# PW_TPS6213x_TestDemo.net
KiCad netlist of a schematic drawn in Altium Designer
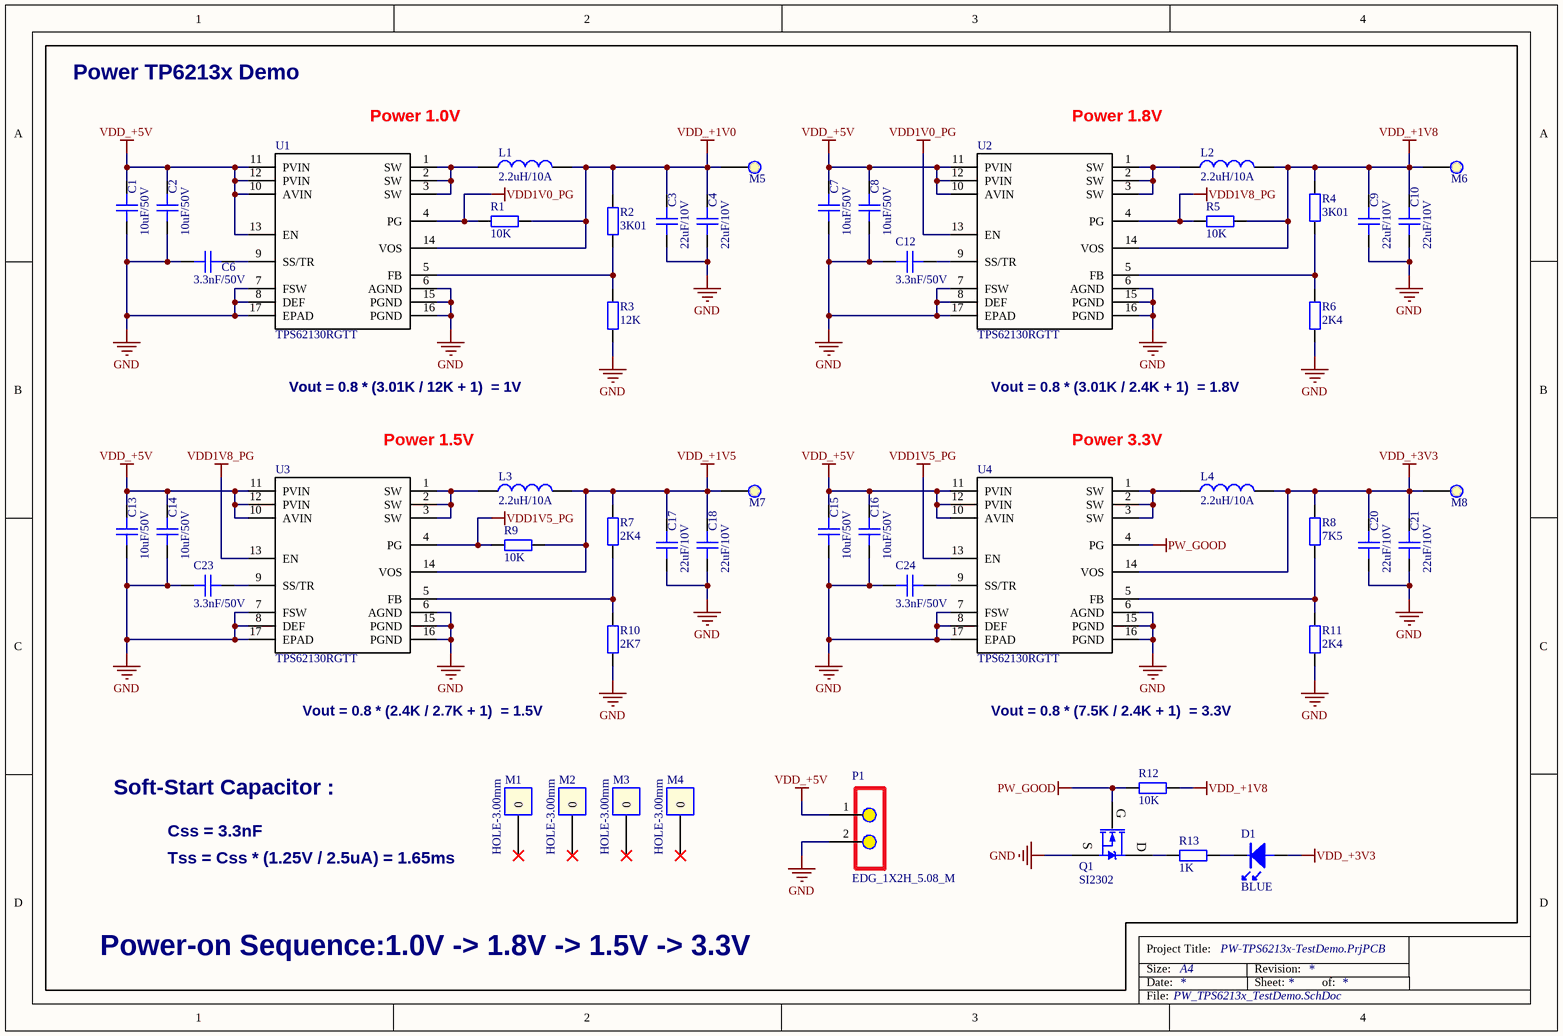
[diagram p0: PW_TPS6213x_TestDemo.SchDoc]

(export (version "E")
  (design (tool "Eeschema 10.0.6"))
  (components
    (comp (ref "C1")
      (value "10uF/50V")
      (footprint "C1206")
      (fields (field (name "Comment") "C_B2_10uF_50V_C1206_20%"))
      (libsource (lib "Fangling DXP Lib") (part "C_B2_10uF_50V_C1206_20%"))
    )
    (comp (ref "C2")
      (value "10uF/50V")
      (footprint "C1206")
      (fields (field (name "Comment") "C_B2_10uF_50V_C1206_20%"))
      (libsource (lib "Fangling DXP Lib") (part "C_B2_10uF_50V_C1206_20%"))
    )
    (comp (ref "C3")
      (value "22uF/10V")
      (footprint "C0805")
      (description "X5R")
      (fields (field (name "Comment") "C_B2_22uF_10V_C0805_20%"))
      (libsource (lib "Fangling DXP Lib") (part "C_B2_22uF_10V_C0805_20%"))
    )
    (comp (ref "C4")
      (value "22uF/10V")
      (footprint "C0805")
      (description "X5R")
      (fields (field (name "Comment") "C_B2_22uF_10V_C0805_20%"))
      (libsource (lib "Fangling DXP Lib") (part "C_B2_22uF_10V_C0805_20%"))
    )
    (comp (ref "C6")
      (value "3.3nF/50V")
      (footprint "C0603")
      (fields (field (name "Comment") "C_B2_3.3nF_50V_C0603_10%"))
      (libsource (lib "UserLib") (part "C_B2_3.3nF_50V_C0603_10%"))
    )
    (comp (ref "C7")
      (value "10uF/50V")
      (footprint "C1206")
      (fields (field (name "Comment") "C_B2_10uF_50V_C1206_20%"))
      (libsource (lib "Fangling DXP Lib") (part "C_B2_10uF_50V_C1206_20%"))
    )
    (comp (ref "C8")
      (value "10uF/50V")
      (footprint "C1206")
      (fields (field (name "Comment") "C_B2_10uF_50V_C1206_20%"))
      (libsource (lib "Fangling DXP Lib") (part "C_B2_10uF_50V_C1206_20%"))
    )
    (comp (ref "C9")
      (value "22uF/10V")
      (footprint "C0805")
      (description "X5R")
      (fields (field (name "Comment") "C_B2_22uF_10V_C0805_20%"))
      (libsource (lib "Fangling DXP Lib") (part "C_B2_22uF_10V_C0805_20%"))
    )
    (comp (ref "C10")
      (value "22uF/10V")
      (footprint "C0805")
      (description "X5R")
      (fields (field (name "Comment") "C_B2_22uF_10V_C0805_20%"))
      (libsource (lib "Fangling DXP Lib") (part "C_B2_22uF_10V_C0805_20%"))
    )
    (comp (ref "C12")
      (value "3.3nF/50V")
      (footprint "C0603")
      (fields (field (name "Comment") "C_B2_3.3nF_50V_C0603_10%"))
      (libsource (lib "UserLib") (part "C_B2_3.3nF_50V_C0603_10%"))
    )
    (comp (ref "C13")
      (value "10uF/50V")
      (footprint "C1206")
      (fields (field (name "Comment") "C_B2_10uF_50V_C1206_20%"))
      (libsource (lib "Fangling DXP Lib") (part "C_B2_10uF_50V_C1206_20%"))
    )
    (comp (ref "C14")
      (value "10uF/50V")
      (footprint "C1206")
      (fields (field (name "Comment") "C_B2_10uF_50V_C1206_20%"))
      (libsource (lib "Fangling DXP Lib") (part "C_B2_10uF_50V_C1206_20%"))
    )
    (comp (ref "C15")
      (value "10uF/50V")
      (footprint "C1206")
      (fields (field (name "Comment") "C_B2_10uF_50V_C1206_20%"))
      (libsource (lib "Fangling DXP Lib") (part "C_B2_10uF_50V_C1206_20%"))
    )
    (comp (ref "C16")
      (value "10uF/50V")
      (footprint "C1206")
      (fields (field (name "Comment") "C_B2_10uF_50V_C1206_20%"))
      (libsource (lib "Fangling DXP Lib") (part "C_B2_10uF_50V_C1206_20%"))
    )
    (comp (ref "C17")
      (value "22uF/10V")
      (footprint "C0805")
      (description "X5R")
      (fields (field (name "Comment") "C_B2_22uF_10V_C0805_20%"))
      (libsource (lib "Fangling DXP Lib") (part "C_B2_22uF_10V_C0805_20%"))
    )
    (comp (ref "C18")
      (value "22uF/10V")
      (footprint "C0805")
      (description "X5R")
      (fields (field (name "Comment") "C_B2_22uF_10V_C0805_20%"))
      (libsource (lib "Fangling DXP Lib") (part "C_B2_22uF_10V_C0805_20%"))
    )
    (comp (ref "C20")
      (value "22uF/10V")
      (footprint "C0805")
      (description "X5R")
      (fields (field (name "Comment") "C_B2_22uF_10V_C0805_20%"))
      (libsource (lib "Fangling DXP Lib") (part "C_B2_22uF_10V_C0805_20%"))
    )
    (comp (ref "C21")
      (value "22uF/10V")
      (footprint "C0805")
      (description "X5R")
      (fields (field (name "Comment") "C_B2_22uF_10V_C0805_20%"))
      (libsource (lib "Fangling DXP Lib") (part "C_B2_22uF_10V_C0805_20%"))
    )
    (comp (ref "C23")
      (value "3.3nF/50V")
      (footprint "C0603")
      (fields (field (name "Comment") "C_B2_3.3nF_50V_C0603_10%"))
      (libsource (lib "UserLib") (part "C_B2_3.3nF_50V_C0603_10%"))
    )
    (comp (ref "C24")
      (value "3.3nF/50V")
      (footprint "C0603")
      (fields (field (name "Comment") "C_B2_3.3nF_50V_C0603_10%"))
      (libsource (lib "UserLib") (part "C_B2_3.3nF_50V_C0603_10%"))
    )
    (comp (ref "D1")
      (value "BLUE")
      (footprint "LED0805")
      (fields (field (name "Comment") "D_D2_LED-BLUE_LED0805"))
      (libsource (lib "Fangling DXP Lib") (part "D_D2_LED-BLUE_LED0805"))
    )
    (comp (ref "L1")
      (value "2.2uH/10A")
      (footprint "L_MWSA0603S")
      (fields (field (name "Comment") "L_C2_2.2uH_10A_MWSA0603S_20%_(MWSA0603S-2R2MT)"))
      (libsource (lib "UserLib") (part "L_C2_2.2uH_10A_MWSA0603S_20%_(MWSA0603S-2R2MT)"))
    )
    (comp (ref "L2")
      (value "2.2uH/10A")
      (footprint "L_MWSA0603S")
      (fields (field (name "Comment") "L_C2_2.2uH_10A_MWSA0603S_20%_(MWSA0603S-2R2MT)"))
      (libsource (lib "UserLib") (part "L_C2_2.2uH_10A_MWSA0603S_20%_(MWSA0603S-2R2MT)"))
    )
    (comp (ref "L3")
      (value "2.2uH/10A")
      (footprint "L_MWSA0603S")
      (fields (field (name "Comment") "L_C2_2.2uH_10A_MWSA0603S_20%_(MWSA0603S-2R2MT)"))
      (libsource (lib "UserLib") (part "L_C2_2.2uH_10A_MWSA0603S_20%_(MWSA0603S-2R2MT)"))
    )
    (comp (ref "L4")
      (value "2.2uH/10A")
      (footprint "L_MWSA0603S")
      (fields (field (name "Comment") "L_C2_2.2uH_10A_MWSA0603S_20%_(MWSA0603S-2R2MT)"))
      (libsource (lib "UserLib") (part "L_C2_2.2uH_10A_MWSA0603S_20%_(MWSA0603S-2R2MT)"))
    )
    (comp (ref "M1")
      (value "HOLE-3.00mm")
      (footprint "M3 3.5x6mm")
      (description "M_HOLE-3.00mm")
      (libsource (lib "Fangling DXP Lib") (part "M_HOLE-3.00mm"))
    )
    (comp (ref "M2")
      (value "HOLE-3.00mm")
      (footprint "M3 3.5x6mm")
      (description "M_HOLE-3.00mm")
      (libsource (lib "Fangling DXP Lib") (part "M_HOLE-3.00mm"))
    )
    (comp (ref "M3")
      (value "HOLE-3.00mm")
      (footprint "M3 3.5x6mm")
      (description "M_HOLE-3.00mm")
      (libsource (lib "Fangling DXP Lib") (part "M_HOLE-3.00mm"))
    )
    (comp (ref "M4")
      (value "HOLE-3.00mm")
      (footprint "M3 3.5x6mm")
      (description "M_HOLE-3.00mm")
      (libsource (lib "Fangling DXP Lib") (part "M_HOLE-3.00mm"))
    )
    (comp (ref "M5")
      (value "M_TP_HOLE")
      (footprint "TP-HOLE")
      (libsource (lib "Fangling DXP Lib") (part "M_TP_HOLE"))
    )
    (comp (ref "M6")
      (value "M_TP_HOLE")
      (footprint "TP-HOLE")
      (libsource (lib "Fangling DXP Lib") (part "M_TP_HOLE"))
    )
    (comp (ref "M7")
      (value "M_TP_HOLE")
      (footprint "TP-HOLE")
      (libsource (lib "Fangling DXP Lib") (part "M_TP_HOLE"))
    )
    (comp (ref "M8")
      (value "M_TP_HOLE")
      (footprint "TP-HOLE")
      (libsource (lib "Fangling DXP Lib") (part "M_TP_HOLE"))
    )
    (comp (ref "P1")
      (value "EDG_1X2H_5.08_M")
      (footprint "KF2EDGK5.08-2P_H")
      (description "Bend foot 5.08EDG")
      (fields (field (name "Comment") "P_EDG_1X2H_5.08_M"))
      (libsource (lib "Fangling DXP Lib") (part "P_EDG_1X2H_5.08_M"))
    )
    (comp (ref "Q1")
      (value "SI2302")
      (footprint "SOT23-3N")
      (description "N-channel FET")
      (fields (field (name "Comment") "Q_B2_SI2302_SOT23-3N"))
      (libsource (lib "Fangling DXP Lib") (part "Q_B2_SI2302_SOT23-3N"))
    )
    (comp (ref "R1")
      (value "10K")
      (footprint "R0603")
      (fields (field (name "Comment") "R_B2_10K_1/10W_R0603_1%"))
      (libsource (lib "Fangling DXP Lib") (part "R_B2_10K_1/10W_R0603_1%"))
    )
    (comp (ref "R2")
      (value "3K01")
      (footprint "R0603")
      (fields (field (name "Comment") "R_B2_3K01_1/10W_R0603_1%"))
      (libsource (lib "Fangling DXP Lib") (part "R_B2_3K01_1/10W_R0603_1%"))
    )
    (comp (ref "R3")
      (value "12K")
      (footprint "R0603")
      (fields (field (name "Comment") "R_B2_12K_1/10W_R0603_1%"))
      (libsource (lib "Fangling DXP Lib") (part "R_B2_12K_1/10W_R0603_1%"))
    )
    (comp (ref "R4")
      (value "3K01")
      (footprint "R0603")
      (fields (field (name "Comment") "R_B2_3K01_1/10W_R0603_1%"))
      (libsource (lib "Fangling DXP Lib") (part "R_B2_3K01_1/10W_R0603_1%"))
    )
    (comp (ref "R5")
      (value "10K")
      (footprint "R0603")
      (fields (field (name "Comment") "R_B2_10K_1/10W_R0603_1%"))
      (libsource (lib "Fangling DXP Lib") (part "R_B2_10K_1/10W_R0603_1%"))
    )
    (comp (ref "R6")
      (value "2K4")
      (footprint "R0603")
      (fields (field (name "Comment") "R_B2_2K4_1/10W_R0603_1%"))
      (libsource (lib "Fangling DXP Lib") (part "R_B2_2K4_1/10W_R0603_1%"))
    )
    (comp (ref "R7")
      (value "2K4")
      (footprint "R0603")
      (fields (field (name "Comment") "R_B2_2K4_1/10W_R0603_1%"))
      (libsource (lib "Fangling DXP Lib") (part "R_B2_2K4_1/10W_R0603_1%"))
    )
    (comp (ref "R8")
      (value "7K5")
      (footprint "R0603")
      (fields (field (name "Comment") "R_B2_7K5_1/10W_R0603_1%"))
      (libsource (lib "Fangling DXP Lib") (part "R_B2_7K5_1/10W_R0603_1%"))
    )
    (comp (ref "R9")
      (value "10K")
      (footprint "R0603")
      (fields (field (name "Comment") "R_B2_10K_1/10W_R0603_1%"))
      (libsource (lib "Fangling DXP Lib") (part "R_B2_10K_1/10W_R0603_1%"))
    )
    (comp (ref "R10")
      (value "2K7")
      (footprint "R0603")
      (fields (field (name "Comment") "R_B2_2K7_1/10W_R0603_1%"))
      (libsource (lib "Fangling DXP Lib") (part "R_B2_2K7_1/10W_R0603_1%"))
    )
    (comp (ref "R11")
      (value "2K4")
      (footprint "R0603")
      (fields (field (name "Comment") "R_B2_2K4_1/10W_R0603_1%"))
      (libsource (lib "Fangling DXP Lib") (part "R_B2_2K4_1/10W_R0603_1%"))
    )
    (comp (ref "R12")
      (value "10K")
      (footprint "R0603")
      (fields (field (name "Comment") "R_B2_10K_1/10W_R0603_1%"))
      (libsource (lib "Fangling DXP Lib") (part "R_B2_10K_1/10W_R0603_1%"))
    )
    (comp (ref "R13")
      (value "1K")
      (footprint "R0603")
      (fields (field (name "Comment") "R_B2_1K_1/10W_R0603_1%"))
      (libsource (lib "Fangling DXP Lib") (part "R_B2_1K_1/10W_R0603_1%"))
    )
    (comp (ref "U1")
      (value "TPS62130RGTT")
      (footprint "QFN16-3X3-EP")
      (description "TPS6213x 3-V to17-V, 3-A Step-Down Converter In 3-mm × 3-mm QFN Package")
      (fields (field (name "Comment") "U_TPS62130RGTT_QFN16"))
      (libsource (lib "UserLib") (part "U_TPS62130RGTT_QFN16"))
    )
    (comp (ref "U2")
      (value "TPS62130RGTT")
      (footprint "QFN16-3X3-EP")
      (description "TPS6213x 3-V to17-V, 3-A Step-Down Converter In 3-mm × 3-mm QFN Package")
      (fields (field (name "Comment") "U_TPS62130RGTT_QFN16"))
      (libsource (lib "UserLib") (part "U_TPS62130RGTT_QFN16"))
    )
    (comp (ref "U3")
      (value "TPS62130RGTT")
      (footprint "QFN16-3X3-EP")
      (description "TPS6213x 3-V to17-V, 3-A Step-Down Converter In 3-mm × 3-mm QFN Package")
      (fields (field (name "Comment") "U_TPS62130RGTT_QFN16"))
      (libsource (lib "UserLib") (part "U_TPS62130RGTT_QFN16"))
    )
    (comp (ref "U4")
      (value "TPS62130RGTT")
      (footprint "QFN16-3X3-EP")
      (description "TPS6213x 3-V to17-V, 3-A Step-Down Converter In 3-mm × 3-mm QFN Package")
      (fields (field (name "Comment") "U_TPS62130RGTT_QFN16"))
      (libsource (lib "UserLib") (part "U_TPS62130RGTT_QFN16"))
    )
  )
  (nets
    (net (code "1") (name "GND") (class "Default")
      (node (ref "C1") (pin "1") (pinfunction "1_1") (pintype "passive"))
      (node (ref "C10") (pin "1") (pinfunction "1_1") (pintype "passive"))
      (node (ref "C12") (pin "1") (pinfunction "1_1") (pintype "passive"))
      (node (ref "C13") (pin "1") (pinfunction "1_1") (pintype "passive"))
      (node (ref "C14") (pin "1") (pinfunction "1_1") (pintype "passive"))
      (node (ref "C15") (pin "1") (pinfunction "1_1") (pintype "passive"))
      (node (ref "C16") (pin "1") (pinfunction "1_1") (pintype "passive"))
      (node (ref "C17") (pin "1") (pinfunction "1_1") (pintype "passive"))
      (node (ref "C18") (pin "1") (pinfunction "1_1") (pintype "passive"))
      (node (ref "C2") (pin "1") (pinfunction "1_1") (pintype "passive"))
      (node (ref "C20") (pin "1") (pinfunction "1_1") (pintype "passive"))
      (node (ref "C21") (pin "1") (pinfunction "1_1") (pintype "passive"))
      (node (ref "C23") (pin "1") (pinfunction "1_1") (pintype "passive"))
      (node (ref "C24") (pin "1") (pinfunction "1_1") (pintype "passive"))
      (node (ref "C3") (pin "1") (pinfunction "1_1") (pintype "passive"))
      (node (ref "C4") (pin "1") (pinfunction "1_1") (pintype "passive"))
      (node (ref "C6") (pin "1") (pinfunction "1_1") (pintype "passive"))
      (node (ref "C7") (pin "1") (pinfunction "1_1") (pintype "passive"))
      (node (ref "C8") (pin "1") (pinfunction "1_1") (pintype "passive"))
      (node (ref "C9") (pin "1") (pinfunction "1_1") (pintype "passive"))
      (node (ref "P1") (pin "2") (pintype "passive"))
      (node (ref "Q1") (pin "2") (pinfunction "S_2") (pintype "passive"))
      (node (ref "R10") (pin "1") (pinfunction "1_1") (pintype "passive"))
      (node (ref "R11") (pin "1") (pinfunction "1_1") (pintype "passive"))
      (node (ref "R3") (pin "1") (pinfunction "1_1") (pintype "passive"))
      (node (ref "R6") (pin "1") (pinfunction "1_1") (pintype "passive"))
      (node (ref "U1") (pin "15") (pinfunction "PGND_15") (pintype "passive"))
      (node (ref "U1") (pin "16") (pinfunction "PGND_16") (pintype "passive"))
      (node (ref "U1") (pin "17") (pinfunction "EPAD_17") (pintype "passive"))
      (node (ref "U1") (pin "6") (pinfunction "AGND_6") (pintype "passive"))
      (node (ref "U1") (pin "7") (pinfunction "FSW_7") (pintype "passive"))
      (node (ref "U1") (pin "8") (pinfunction "DEF_8") (pintype "passive"))
      (node (ref "U2") (pin "15") (pinfunction "PGND_15") (pintype "passive"))
      (node (ref "U2") (pin "16") (pinfunction "PGND_16") (pintype "passive"))
      (node (ref "U2") (pin "17") (pinfunction "EPAD_17") (pintype "passive"))
      (node (ref "U2") (pin "6") (pinfunction "AGND_6") (pintype "passive"))
      (node (ref "U2") (pin "7") (pinfunction "FSW_7") (pintype "passive"))
      (node (ref "U2") (pin "8") (pinfunction "DEF_8") (pintype "passive"))
      (node (ref "U3") (pin "15") (pinfunction "PGND_15") (pintype "passive"))
      (node (ref "U3") (pin "16") (pinfunction "PGND_16") (pintype "passive"))
      (node (ref "U3") (pin "17") (pinfunction "EPAD_17") (pintype "passive"))
      (node (ref "U3") (pin "6") (pinfunction "AGND_6") (pintype "passive"))
      (node (ref "U3") (pin "7") (pinfunction "FSW_7") (pintype "passive"))
      (node (ref "U3") (pin "8") (pinfunction "DEF_8") (pintype "passive"))
      (node (ref "U4") (pin "15") (pinfunction "PGND_15") (pintype "passive"))
      (node (ref "U4") (pin "16") (pinfunction "PGND_16") (pintype "passive"))
      (node (ref "U4") (pin "17") (pinfunction "EPAD_17") (pintype "passive"))
      (node (ref "U4") (pin "6") (pinfunction "AGND_6") (pintype "passive"))
      (node (ref "U4") (pin "7") (pinfunction "FSW_7") (pintype "passive"))
      (node (ref "U4") (pin "8") (pinfunction "DEF_8") (pintype "passive"))
    )
    (net (code "2") (name "Net-(D1-K)") (class "Default")
      (node (ref "D1") (pin "2") (pinfunction "K_2") (pintype "passive"))
      (node (ref "R13") (pin "2") (pinfunction "2_2") (pintype "passive"))
    )
    (net (code "3") (name "Net-(L1-Pad1)") (class "Default")
      (node (ref "L1") (pin "1") (pinfunction "1_1") (pintype "passive"))
      (node (ref "U1") (pin "1") (pinfunction "SW_1") (pintype "passive"))
      (node (ref "U1") (pin "2") (pinfunction "SW_2") (pintype "passive"))
      (node (ref "U1") (pin "3") (pinfunction "SW_3") (pintype "passive"))
    )
    (net (code "4") (name "Net-(L2-Pad1)") (class "Default")
      (node (ref "L2") (pin "1") (pinfunction "1_1") (pintype "passive"))
      (node (ref "U2") (pin "1") (pinfunction "SW_1") (pintype "passive"))
      (node (ref "U2") (pin "2") (pinfunction "SW_2") (pintype "passive"))
      (node (ref "U2") (pin "3") (pinfunction "SW_3") (pintype "passive"))
    )
    (net (code "5") (name "Net-(L3-Pad1)") (class "Default")
      (node (ref "L3") (pin "1") (pinfunction "1_1") (pintype "passive"))
      (node (ref "U3") (pin "1") (pinfunction "SW_1") (pintype "passive"))
      (node (ref "U3") (pin "2") (pinfunction "SW_2") (pintype "passive"))
      (node (ref "U3") (pin "3") (pinfunction "SW_3") (pintype "passive"))
    )
    (net (code "6") (name "Net-(L4-Pad1)") (class "Default")
      (node (ref "L4") (pin "1") (pinfunction "1_1") (pintype "passive"))
      (node (ref "U4") (pin "1") (pinfunction "SW_1") (pintype "passive"))
      (node (ref "U4") (pin "2") (pinfunction "SW_2") (pintype "passive"))
      (node (ref "U4") (pin "3") (pinfunction "SW_3") (pintype "passive"))
    )
    (net (code "7") (name "Net-(Q1-D)") (class "Default")
      (node (ref "Q1") (pin "3") (pinfunction "D_3") (pintype "passive"))
      (node (ref "R13") (pin "1") (pinfunction "1_1") (pintype "passive"))
    )
    (net (code "8") (name "Net-(U1-FB)") (class "Default")
      (node (ref "R2") (pin "1") (pinfunction "1_1") (pintype "passive"))
      (node (ref "R3") (pin "2") (pinfunction "2_2") (pintype "passive"))
      (node (ref "U1") (pin "5") (pinfunction "FB_5") (pintype "passive"))
    )
    (net (code "9") (name "Net-(U1-SS{slash}TR)") (class "Default")
      (node (ref "C6") (pin "2") (pinfunction "2_2") (pintype "passive"))
      (node (ref "U1") (pin "9") (pinfunction "SS/TR_9") (pintype "passive"))
    )
    (net (code "10") (name "Net-(U2-FB)") (class "Default")
      (node (ref "R4") (pin "1") (pinfunction "1_1") (pintype "passive"))
      (node (ref "R6") (pin "2") (pinfunction "2_2") (pintype "passive"))
      (node (ref "U2") (pin "5") (pinfunction "FB_5") (pintype "passive"))
    )
    (net (code "11") (name "Net-(U2-SS{slash}TR)") (class "Default")
      (node (ref "C12") (pin "2") (pinfunction "2_2") (pintype "passive"))
      (node (ref "U2") (pin "9") (pinfunction "SS/TR_9") (pintype "passive"))
    )
    (net (code "12") (name "Net-(U3-FB)") (class "Default")
      (node (ref "R10") (pin "2") (pinfunction "2_2") (pintype "passive"))
      (node (ref "R7") (pin "1") (pinfunction "1_1") (pintype "passive"))
      (node (ref "U3") (pin "5") (pinfunction "FB_5") (pintype "passive"))
    )
    (net (code "13") (name "Net-(U3-SS{slash}TR)") (class "Default")
      (node (ref "C23") (pin "2") (pinfunction "2_2") (pintype "passive"))
      (node (ref "U3") (pin "9") (pinfunction "SS/TR_9") (pintype "passive"))
    )
    (net (code "14") (name "Net-(U4-FB)") (class "Default")
      (node (ref "R11") (pin "2") (pinfunction "2_2") (pintype "passive"))
      (node (ref "R8") (pin "1") (pinfunction "1_1") (pintype "passive"))
      (node (ref "U4") (pin "5") (pinfunction "FB_5") (pintype "passive"))
    )
    (net (code "15") (name "Net-(U4-SS{slash}TR)") (class "Default")
      (node (ref "C24") (pin "2") (pinfunction "2_2") (pintype "passive"))
      (node (ref "U4") (pin "9") (pinfunction "SS/TR_9") (pintype "passive"))
    )
    (net (code "16") (name "PW_GOOD") (class "Default")
      (node (ref "Q1") (pin "1") (pinfunction "G_1") (pintype "passive"))
      (node (ref "R12") (pin "2") (pinfunction "2_2") (pintype "passive"))
      (node (ref "U4") (pin "4") (pinfunction "PG_4") (pintype "passive"))
    )
    (net (code "17") (name "VDD1V0_PG") (class "Default")
      (node (ref "R1") (pin "1") (pinfunction "1_1") (pintype "passive"))
      (node (ref "U1") (pin "4") (pinfunction "PG_4") (pintype "passive"))
      (node (ref "U2") (pin "13") (pinfunction "EN_13") (pintype "passive"))
    )
    (net (code "18") (name "VDD1V5_PG") (class "Default")
      (node (ref "R9") (pin "1") (pinfunction "1_1") (pintype "passive"))
      (node (ref "U3") (pin "4") (pinfunction "PG_4") (pintype "passive"))
      (node (ref "U4") (pin "13") (pinfunction "EN_13") (pintype "passive"))
    )
    (net (code "19") (name "VDD1V8_PG") (class "Default")
      (node (ref "R5") (pin "1") (pinfunction "1_1") (pintype "passive"))
      (node (ref "U2") (pin "4") (pinfunction "PG_4") (pintype "passive"))
      (node (ref "U3") (pin "13") (pinfunction "EN_13") (pintype "passive"))
    )
    (net (code "20") (name "VDD_+1V0") (class "Default")
      (node (ref "C3") (pin "2") (pinfunction "2_2") (pintype "passive"))
      (node (ref "C4") (pin "2") (pinfunction "2_2") (pintype "passive"))
      (node (ref "L1") (pin "2") (pinfunction "2_2") (pintype "passive"))
      (node (ref "M5") (pin "1") (pinfunction "1_1") (pintype "passive"))
      (node (ref "R1") (pin "2") (pinfunction "2_2") (pintype "passive"))
      (node (ref "R2") (pin "2") (pinfunction "2_2") (pintype "passive"))
      (node (ref "U1") (pin "14") (pinfunction "VOS_14") (pintype "passive"))
    )
    (net (code "21") (name "VDD_+1V5") (class "Default")
      (node (ref "C17") (pin "2") (pinfunction "2_2") (pintype "passive"))
      (node (ref "C18") (pin "2") (pinfunction "2_2") (pintype "passive"))
      (node (ref "L3") (pin "2") (pinfunction "2_2") (pintype "passive"))
      (node (ref "M7") (pin "1") (pinfunction "1_1") (pintype "passive"))
      (node (ref "R7") (pin "2") (pinfunction "2_2") (pintype "passive"))
      (node (ref "R9") (pin "2") (pinfunction "2_2") (pintype "passive"))
      (node (ref "U3") (pin "14") (pinfunction "VOS_14") (pintype "passive"))
    )
    (net (code "22") (name "VDD_+1V8") (class "Default")
      (node (ref "C10") (pin "2") (pinfunction "2_2") (pintype "passive"))
      (node (ref "C9") (pin "2") (pinfunction "2_2") (pintype "passive"))
      (node (ref "L2") (pin "2") (pinfunction "2_2") (pintype "passive"))
      (node (ref "M6") (pin "1") (pinfunction "1_1") (pintype "passive"))
      (node (ref "R12") (pin "1") (pinfunction "1_1") (pintype "passive"))
      (node (ref "R4") (pin "2") (pinfunction "2_2") (pintype "passive"))
      (node (ref "R5") (pin "2") (pinfunction "2_2") (pintype "passive"))
      (node (ref "U2") (pin "14") (pinfunction "VOS_14") (pintype "passive"))
    )
    (net (code "23") (name "VDD_+3V3") (class "Default")
      (node (ref "C20") (pin "2") (pinfunction "2_2") (pintype "passive"))
      (node (ref "C21") (pin "2") (pinfunction "2_2") (pintype "passive"))
      (node (ref "D1") (pin "1") (pinfunction "A_1") (pintype "passive"))
      (node (ref "L4") (pin "2") (pinfunction "2_2") (pintype "passive"))
      (node (ref "M8") (pin "1") (pinfunction "1_1") (pintype "passive"))
      (node (ref "R8") (pin "2") (pinfunction "2_2") (pintype "passive"))
      (node (ref "U4") (pin "14") (pinfunction "VOS_14") (pintype "passive"))
    )
    (net (code "24") (name "VDD_+5V") (class "Default")
      (node (ref "C1") (pin "2") (pinfunction "2_2") (pintype "passive"))
      (node (ref "C13") (pin "2") (pinfunction "2_2") (pintype "passive"))
      (node (ref "C14") (pin "2") (pinfunction "2_2") (pintype "passive"))
      (node (ref "C15") (pin "2") (pinfunction "2_2") (pintype "passive"))
      (node (ref "C16") (pin "2") (pinfunction "2_2") (pintype "passive"))
      (node (ref "C2") (pin "2") (pinfunction "2_2") (pintype "passive"))
      (node (ref "C7") (pin "2") (pinfunction "2_2") (pintype "passive"))
      (node (ref "C8") (pin "2") (pinfunction "2_2") (pintype "passive"))
      (node (ref "P1") (pin "1") (pintype "passive"))
      (node (ref "U1") (pin "10") (pinfunction "AVIN_10") (pintype "passive"))
      (node (ref "U1") (pin "11") (pinfunction "PVIN_11") (pintype "passive"))
      (node (ref "U1") (pin "12") (pinfunction "PVIN_12") (pintype "passive"))
      (node (ref "U1") (pin "13") (pinfunction "EN_13") (pintype "passive"))
      (node (ref "U2") (pin "10") (pinfunction "AVIN_10") (pintype "passive"))
      (node (ref "U2") (pin "11") (pinfunction "PVIN_11") (pintype "passive"))
      (node (ref "U2") (pin "12") (pinfunction "PVIN_12") (pintype "passive"))
      (node (ref "U3") (pin "10") (pinfunction "AVIN_10") (pintype "passive"))
      (node (ref "U3") (pin "11") (pinfunction "PVIN_11") (pintype "passive"))
      (node (ref "U3") (pin "12") (pinfunction "PVIN_12") (pintype "passive"))
      (node (ref "U4") (pin "10") (pinfunction "AVIN_10") (pintype "passive"))
      (node (ref "U4") (pin "11") (pinfunction "PVIN_11") (pintype "passive"))
      (node (ref "U4") (pin "12") (pinfunction "PVIN_12") (pintype "passive"))
    )
    (net (code "25") (name "unconnected-(M1-Pad0)") (class "Default")
      (node (ref "M1") (pin "0") (pinfunction "0_0") (pintype "passive+no_connect"))
    )
    (net (code "26") (name "unconnected-(M2-Pad0)") (class "Default")
      (node (ref "M2") (pin "0") (pinfunction "0_0") (pintype "passive+no_connect"))
    )
    (net (code "27") (name "unconnected-(M3-Pad0)") (class "Default")
      (node (ref "M3") (pin "0") (pinfunction "0_0") (pintype "passive+no_connect"))
    )
    (net (code "28") (name "unconnected-(M4-Pad0)") (class "Default")
      (node (ref "M4") (pin "0") (pinfunction "0_0") (pintype "passive+no_connect"))
    )
  )
)
